# SDcard_eMMC.net
KiCad netlist of a schematic drawn in Altium Designer
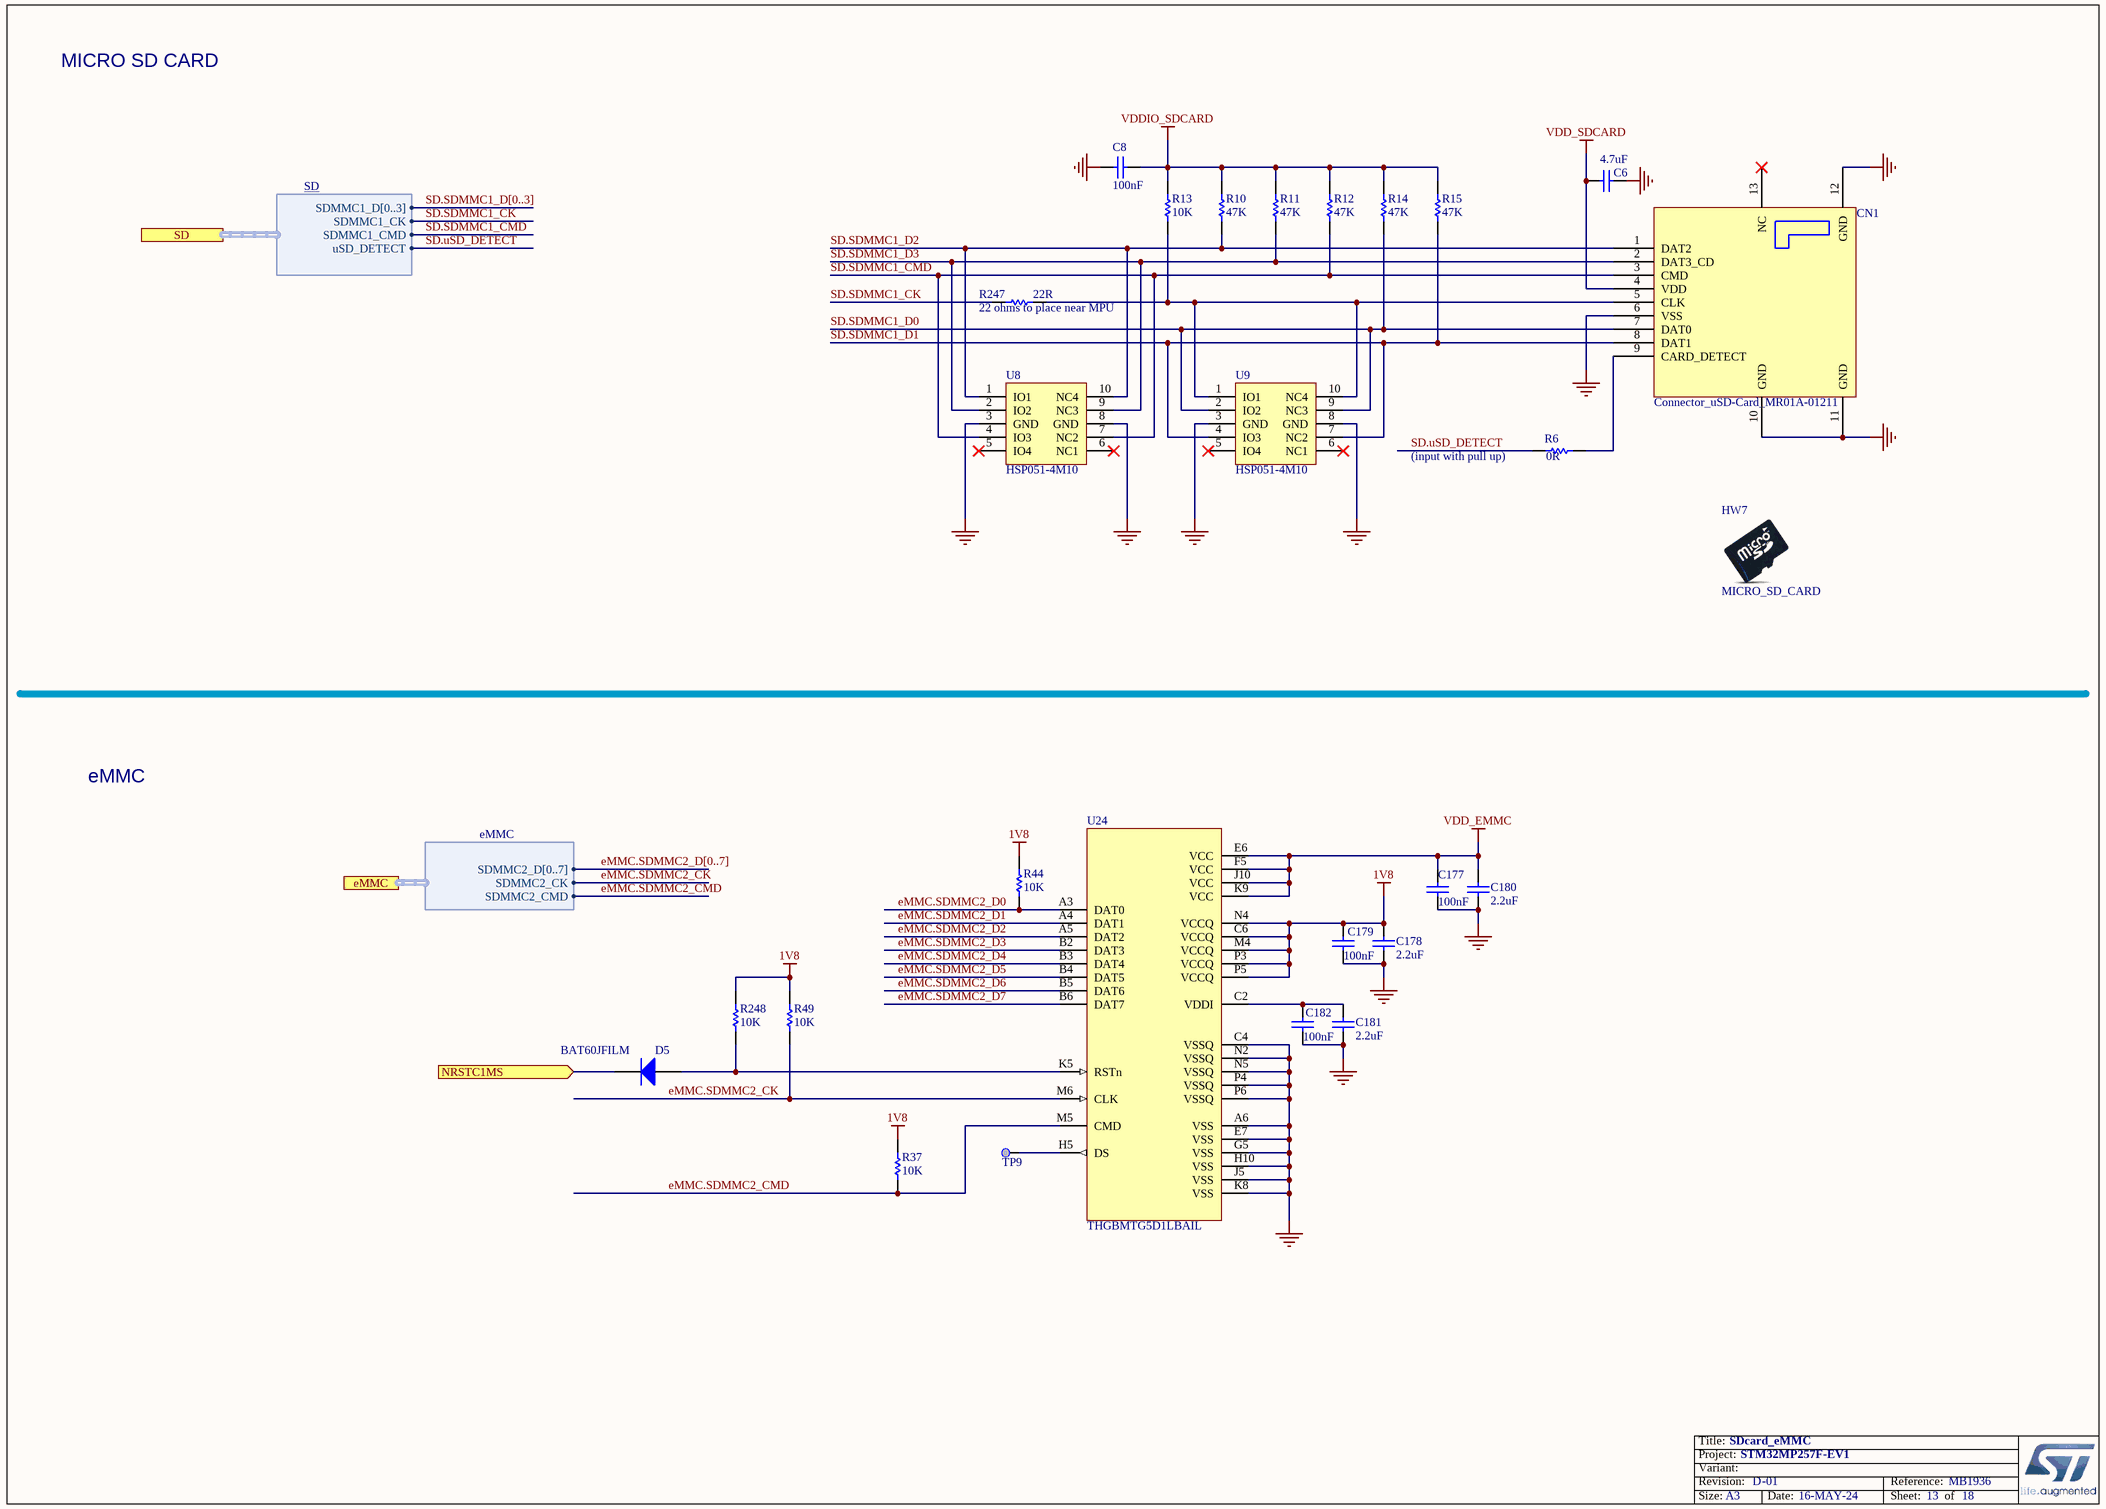
[diagram p0: SDcard_eMMC.SchDoc]

(export (version "E")
  (design (tool "Eeschema 10.0.6"))
  (components
    (comp (ref "C6")
      (value "4.7uF")
      (footprint "MCD_PARTS:C0402")
      (description "Capacitor, MLCC, 4.7uF, 6V3, X5R, 20%, 0402, T=0,5mm")
      (fields
        (field (name "INTERNAL_PART_NUMBER") "MCD-01356")
        (field (name "MANUFACTURER_PART_NUMBER") "GRM155R60J475ME47")
        (field (name "PROVIDED_BY") "SUBCO")
      )
      (libsource (lib "MCD_PARTS_database") (part "Capacitor"))
    )
    (comp (ref "C8")
      (value "100nF")
      (footprint "MCD_PARTS:C0402")
      (description "Capacitor, MLCC, 100nF, 16V, X7R, +/-10%, 0402, T=0.5mm")
      (fields (field (name "INTERNAL_PART_NUMBER") "MCD-00006") (field (name "MANUFACTURER") "YAGEO"))
      (libsource (lib "MCD_PARTS_database") (part "Capacitor"))
    )
    (comp (ref "C177")
      (value "100nF")
      (footprint "MCD_PARTS:C0402")
      (description "Capacitor, MLCC, 100nF, 16V, X7R, +/-10%, 0402, T=0.5mm")
      (fields (field (name "INTERNAL_PART_NUMBER") "MCD-00006") (field (name "MANUFACTURER") "YAGEO"))
      (libsource (lib "MCD_PARTS_database") (part "Capacitor"))
    )
    (comp (ref "C178")
      (value "2.2uF")
      (footprint "MCD_PARTS:C0402")
      (description "Capacitor, MLCC, 2.2uF, 6.3V, X5R, +/-10%, 0402, T=0.5mm")
      (fields (field (name "INTERNAL_PART_NUMBER") "MCD-02606") (field (name "MANUFACTURER") "YAGEO"))
      (libsource (lib "MCD_PARTS_database") (part "Capacitor"))
    )
    (comp (ref "C179")
      (value "100nF")
      (footprint "MCD_PARTS:C0402")
      (description "Capacitor, MLCC, 100nF, 16V, X7R, +/-10%, 0402, T=0.5mm")
      (fields (field (name "INTERNAL_PART_NUMBER") "MCD-00006") (field (name "MANUFACTURER") "YAGEO"))
      (libsource (lib "MCD_PARTS_database") (part "Capacitor"))
    )
    (comp (ref "C180")
      (value "2.2uF")
      (footprint "MCD_PARTS:C0402")
      (description "Capacitor, MLCC, 2.2uF, 6.3V, X5R, +/-10%, 0402, T=0.5mm")
      (fields (field (name "INTERNAL_PART_NUMBER") "MCD-02606") (field (name "MANUFACTURER") "YAGEO"))
      (libsource (lib "MCD_PARTS_database") (part "Capacitor"))
    )
    (comp (ref "C181")
      (value "2.2uF")
      (footprint "MCD_PARTS:C0402")
      (description "Capacitor, MLCC, 2.2uF, 6.3V, X5R, +/-10%, 0402, T=0.5mm")
      (fields (field (name "INTERNAL_PART_NUMBER") "MCD-02606") (field (name "MANUFACTURER") "YAGEO"))
      (libsource (lib "MCD_PARTS_database") (part "Capacitor"))
    )
    (comp (ref "C182")
      (value "100nF")
      (footprint "MCD_PARTS:C0402")
      (description "Capacitor, MLCC, 100nF, 16V, X7R, +/-10%, 0402, T=0.5mm")
      (fields (field (name "INTERNAL_PART_NUMBER") "MCD-00006") (field (name "MANUFACTURER") "YAGEO"))
      (libsource (lib "MCD_PARTS_database") (part "Capacitor"))
    )
    (comp (ref "CN1")
      (value "Connector_uSD-Card_MR01A-01211")
      (footprint "MCD_PARTS:CON_MICROSD_ATOM_MR01A-01211")
      (description "Connector_uSD Card, Top Mnt Push-Push")
      (fields (field (name "INTERNAL_PART_NUMBER") "MCD-00653") (field (name "MANUFACTURER") "ATOM"))
      (libsource (lib "MCD_PARTS_database") (part "MR01A-01211"))
    )
    (comp (ref "D5")
      (value "BAT60JFILM")
      (footprint "MCD_PARTS:DIO_SOD323")
      (fields
        (field (name "INTERNAL_PART_NUMBER") "MCD-00034")
        (field (name "BMS_PART_NUMBER") "9151097")
        (field (name "MANUFACTURER") "STMICROELECTRONICS")
      )
      (libsource (lib "MCD_PARTS_database") (part "BAT60JFILM"))
    )
    (comp (ref "HW7")
      (value "MICRO_SD_CARD")
      (description "MICRO_SD_CARD, SANDISK, 16GB, Class10, 3V")
      (fields (field (name "INTERNAL_PART_NUMBER") "MCD-03307") (field (name "MANUFACTURER") "SANDISK"))
      (libsource (lib "MCD_PARTS_database") (part "Micro_SD_card"))
    )
    (comp (ref "R6")
      (value "0R")
      (footprint "MCD_PARTS:R0402")
      (description "Resistor,0R,0402,5%,1/16W")
      (fields
        (field (name "INTERNAL_PART_NUMBER") "MCD-00052")
        (field (name "MANUFACTURER_PART_NUMBER") "RC0402JR-070RL")
        (field (name "PROVIDED_BY") "SUBCO")
      )
      (libsource (lib "MCD_PARTS_database") (part "Resistor"))
    )
    (comp (ref "R10")
      (value "47K")
      (footprint "MCD_PARTS:R0402")
      (description "Resistor,47K,0402,1%,1/16W")
      (fields
        (field (name "INTERNAL_PART_NUMBER") "MCD-00063")
        (field (name "MANUFACTURER_PART_NUMBER") "RC0402FR-0747KL")
        (field (name "PROVIDED_BY") "SUBCO")
      )
      (libsource (lib "MCD_PARTS_database") (part "Resistor"))
    )
    (comp (ref "R11")
      (value "47K")
      (footprint "MCD_PARTS:R0402")
      (description "Resistor,47K,0402,1%,1/16W")
      (fields
        (field (name "INTERNAL_PART_NUMBER") "MCD-00063")
        (field (name "MANUFACTURER_PART_NUMBER") "RC0402FR-0747KL")
        (field (name "PROVIDED_BY") "SUBCO")
      )
      (libsource (lib "MCD_PARTS_database") (part "Resistor"))
    )
    (comp (ref "R12")
      (value "47K")
      (footprint "MCD_PARTS:R0402")
      (description "Resistor,47K,0402,1%,1/16W")
      (fields
        (field (name "INTERNAL_PART_NUMBER") "MCD-00063")
        (field (name "MANUFACTURER_PART_NUMBER") "RC0402FR-0747KL")
        (field (name "PROVIDED_BY") "SUBCO")
      )
      (libsource (lib "MCD_PARTS_database") (part "Resistor"))
    )
    (comp (ref "R13")
      (value "10K")
      (footprint "MCD_PARTS:R0402")
      (description "Resistor,10K,0402,1%,1/16W")
      (fields
        (field (name "INTERNAL_PART_NUMBER") "MCD-00053")
        (field (name "MANUFACTURER_PART_NUMBER") "RC0402FR-0710KL")
        (field (name "PROVIDED_BY") "SUBCO")
      )
      (libsource (lib "MCD_PARTS_database") (part "Resistor"))
    )
    (comp (ref "R14")
      (value "47K")
      (footprint "MCD_PARTS:R0402")
      (description "Resistor,47K,0402,1%,1/16W")
      (fields
        (field (name "INTERNAL_PART_NUMBER") "MCD-00063")
        (field (name "MANUFACTURER_PART_NUMBER") "RC0402FR-0747KL")
        (field (name "PROVIDED_BY") "SUBCO")
      )
      (libsource (lib "MCD_PARTS_database") (part "Resistor"))
    )
    (comp (ref "R15")
      (value "47K")
      (footprint "MCD_PARTS:R0402")
      (description "Resistor,47K,0402,1%,1/16W")
      (fields
        (field (name "INTERNAL_PART_NUMBER") "MCD-00063")
        (field (name "MANUFACTURER_PART_NUMBER") "RC0402FR-0747KL")
        (field (name "PROVIDED_BY") "SUBCO")
      )
      (libsource (lib "MCD_PARTS_database") (part "Resistor"))
    )
    (comp (ref "R37")
      (value "10K")
      (footprint "MCD_PARTS:R0402")
      (description "Resistor,10K,0402,1%,1/16W")
      (fields
        (field (name "INTERNAL_PART_NUMBER") "MCD-00053")
        (field (name "MANUFACTURER_PART_NUMBER") "RC0402FR-0710KL")
        (field (name "PROVIDED_BY") "SUBCO")
      )
      (libsource (lib "MCD_PARTS_database") (part "Resistor"))
    )
    (comp (ref "R44")
      (value "10K")
      (footprint "MCD_PARTS:R0402")
      (description "Resistor,10K,0402,1%,1/16W")
      (fields
        (field (name "INTERNAL_PART_NUMBER") "MCD-00053")
        (field (name "MANUFACTURER_PART_NUMBER") "RC0402FR-0710KL")
        (field (name "PROVIDED_BY") "SUBCO")
      )
      (libsource (lib "MCD_PARTS_database") (part "Resistor"))
    )
    (comp (ref "R49")
      (value "10K")
      (footprint "MCD_PARTS:R0402")
      (description "Resistor,10K,0402,1%,1/16W")
      (fields
        (field (name "INTERNAL_PART_NUMBER") "MCD-00053")
        (field (name "MANUFACTURER_PART_NUMBER") "RC0402FR-0710KL")
        (field (name "PROVIDED_BY") "SUBCO")
      )
      (libsource (lib "MCD_PARTS_database") (part "Resistor"))
    )
    (comp (ref "R247")
      (value "22R")
      (footprint "MCD_PARTS:R0201_H0P23")
      (description "Resistor, 22R, 0201, +/-1%, 1/20W")
      (fields
        (field (name "INTERNAL_PART_NUMBER") "MCD-02978")
        (field (name "MANUFACTURER_PART_NUMBER") "RC0201FR-0722RL")
      )
      (libsource (lib "MCD_PARTS_database") (part "Resistor"))
    )
    (comp (ref "R248")
      (value "10K")
      (footprint "MCD_PARTS:R0402")
      (description "Resistor,10K,0402,1%,1/16W")
      (fields
        (field (name "INTERNAL_PART_NUMBER") "MCD-00053")
        (field (name "MANUFACTURER_PART_NUMBER") "RC0402FR-0710KL")
        (field (name "PROVIDED_BY") "SUBCO")
      )
      (libsource (lib "MCD_PARTS_database") (part "Resistor"))
    )
    (comp (ref "TP9")
      (value "Test Point")
      (footprint "MCD_PARTS:TP_SMD_1MM")
      (description "Test Point 1mm")
      (fields
        (field (name "INTERNAL_PART_NUMBER") "MCD-00074")
        (field (name "MANUFACTURER_PART_NUMBER") "n/a")
      )
      (libsource (lib "MCD_PARTS_database") (part "Test Point"))
    )
    (comp (ref "U8")
      (value "HSP051-4M10")
      (footprint "MCD_PARTS:ESD_UQFN-10L_2P5X1_P050")
      (description "4-line ESD protection for high speed lines")
      (fields
        (field (name "INTERNAL_PART_NUMBER") "MCD-00667")
        (field (name "MANUFACTURER") "STMICROELECTRONICS")
        (field (name "PROVIDED_BY") "SUBCO with ST control")
      )
      (libsource (lib "MCD_PARTS_database") (part "HSP051-4M10"))
    )
    (comp (ref "U9")
      (value "HSP051-4M10")
      (footprint "MCD_PARTS:ESD_UQFN-10L_2P5X1_P050")
      (description "4-line ESD protection for high speed lines")
      (fields
        (field (name "INTERNAL_PART_NUMBER") "MCD-00667")
        (field (name "MANUFACTURER") "STMICROELECTRONICS")
        (field (name "PROVIDED_BY") "SUBCO with ST control")
      )
      (libsource (lib "MCD_PARTS_database") (part "HSP051-4M10"))
    )
    (comp (ref "U24")
      (value "THGBMTG5D1LBAIL")
      (footprint "MCD_PARTS:ICC_P-WFBGA153_13X11P5_P050")
      (description "Memory, eMMC, 4GB, 15nm ,WFBGA , 153 pins")
      (fields (field (name "INTERNAL_PART_NUMBER") "MCD-02799") (field (name "MANUFACTURER") "KIOXIA"))
      (libsource (lib "MCD_PARTS_database") (part "eMMC_THGBMTG5D1LBAIL"))
    )
  )
  (nets
    (net (code "3") (name "/NRSTC1MS") (class "Default")
      (node (ref "D5") (pin "2") (pinfunction "K_2") (pintype "passive"))
    )
    (net (code "4") (name "/SD.SDMMC1_CK") (class "Default")
      (node (ref "R247") (pin "1") (pinfunction "1_1") (pintype "passive"))
    )
    (net (code "5") (name "/SD.SDMMC1_CMD") (class "Default")
      (node (ref "CN1") (pin "3") (pinfunction "CMD_3") (pintype "passive"))
      (node (ref "R12") (pin "1") (pinfunction "1_1") (pintype "passive"))
      (node (ref "U8") (pin "4") (pinfunction "IO3_4") (pintype "passive"))
      (node (ref "U8") (pin "7") (pinfunction "NC2_7") (pintype "passive"))
    )
    (net (code "6") (name "/SD.SDMMC1_D0") (class "Default")
      (node (ref "CN1") (pin "7") (pinfunction "DAT0_7") (pintype "passive"))
      (node (ref "R14") (pin "1") (pinfunction "1_1") (pintype "passive"))
      (node (ref "U9") (pin "2") (pinfunction "IO2_2") (pintype "passive"))
      (node (ref "U9") (pin "9") (pinfunction "NC3_9") (pintype "passive"))
    )
    (net (code "7") (name "/SD.SDMMC1_D1") (class "Default")
      (node (ref "CN1") (pin "8") (pinfunction "DAT1_8") (pintype "passive"))
      (node (ref "R15") (pin "1") (pinfunction "1_1") (pintype "passive"))
      (node (ref "U9") (pin "4") (pinfunction "IO3_4") (pintype "passive"))
      (node (ref "U9") (pin "7") (pinfunction "NC2_7") (pintype "passive"))
    )
    (net (code "8") (name "/SD.SDMMC1_D2") (class "Default")
      (node (ref "CN1") (pin "1") (pinfunction "DAT2_1") (pintype "passive"))
      (node (ref "R10") (pin "1") (pinfunction "1_1") (pintype "passive"))
      (node (ref "U8") (pin "1") (pinfunction "IO1_1") (pintype "passive"))
      (node (ref "U8") (pin "10") (pinfunction "NC4_10") (pintype "passive"))
    )
    (net (code "9") (name "/SD.SDMMC1_D3") (class "Default")
      (node (ref "CN1") (pin "2") (pinfunction "DAT3_CD_2") (pintype "passive"))
      (node (ref "R11") (pin "1") (pinfunction "1_1") (pintype "passive"))
      (node (ref "U8") (pin "2") (pinfunction "IO2_2") (pintype "passive"))
      (node (ref "U8") (pin "9") (pinfunction "NC3_9") (pintype "passive"))
    )
    (net (code "10") (name "/SD.uSD_DETECT") (class "Default")
      (node (ref "R6") (pin "1") (pinfunction "1_1") (pintype "passive"))
    )
    (net (code "12") (name "/eMMC.SDMMC2_CK") (class "Default")
      (node (ref "R49") (pin "1") (pinfunction "1_1") (pintype "passive"))
      (node (ref "U24") (pin "M6") (pinfunction "CLK_M6") (pintype "input"))
    )
    (net (code "13") (name "/eMMC.SDMMC2_CMD") (class "Default")
      (node (ref "R37") (pin "1") (pinfunction "1_1") (pintype "passive"))
      (node (ref "U24") (pin "M5") (pinfunction "CMD_M5") (pintype "passive"))
    )
    (net (code "14") (name "/eMMC.SDMMC2_D0") (class "Default")
      (node (ref "R44") (pin "1") (pinfunction "1_1") (pintype "passive"))
      (node (ref "U24") (pin "A3") (pinfunction "DAT0_A3") (pintype "passive"))
    )
    (net (code "15") (name "/eMMC.SDMMC2_D1") (class "Default")
      (node (ref "U24") (pin "A4") (pinfunction "DAT1_A4") (pintype "passive"))
    )
    (net (code "16") (name "/eMMC.SDMMC2_D2") (class "Default")
      (node (ref "U24") (pin "A5") (pinfunction "DAT2_A5") (pintype "passive"))
    )
    (net (code "17") (name "/eMMC.SDMMC2_D3") (class "Default")
      (node (ref "U24") (pin "B2") (pinfunction "DAT3_B2") (pintype "passive"))
    )
    (net (code "18") (name "/eMMC.SDMMC2_D4") (class "Default")
      (node (ref "U24") (pin "B3") (pinfunction "DAT4_B3") (pintype "passive"))
    )
    (net (code "19") (name "/eMMC.SDMMC2_D5") (class "Default")
      (node (ref "U24") (pin "B4") (pinfunction "DAT5_B4") (pintype "passive"))
    )
    (net (code "20") (name "/eMMC.SDMMC2_D6") (class "Default")
      (node (ref "U24") (pin "B5") (pinfunction "DAT6_B5") (pintype "passive"))
    )
    (net (code "21") (name "/eMMC.SDMMC2_D7") (class "Default")
      (node (ref "U24") (pin "B6") (pinfunction "DAT7_B6") (pintype "passive"))
    )
    (net (code "25") (name "1V8") (class "Default")
      (node (ref "C178") (pin "2") (pinfunction "2_2") (pintype "passive"))
      (node (ref "C179") (pin "2") (pinfunction "2_2") (pintype "passive"))
      (node (ref "R248") (pin "2") (pinfunction "2_2") (pintype "passive"))
      (node (ref "R37") (pin "2") (pinfunction "2_2") (pintype "passive"))
      (node (ref "R44") (pin "2") (pinfunction "2_2") (pintype "passive"))
      (node (ref "R49") (pin "2") (pinfunction "2_2") (pintype "passive"))
      (node (ref "U24") (pin "C6") (pinfunction "VCCQ_C6") (pintype "passive"))
      (node (ref "U24") (pin "M4") (pinfunction "VCCQ_M4") (pintype "passive"))
      (node (ref "U24") (pin "N4") (pinfunction "VCCQ_N4") (pintype "passive"))
      (node (ref "U24") (pin "P3") (pinfunction "VCCQ_P3") (pintype "passive"))
      (node (ref "U24") (pin "P5") (pinfunction "VCCQ_P5") (pintype "passive"))
    )
    (net (code "26") (name "GND") (class "Default")
      (node (ref "C177") (pin "1") (pinfunction "1_1") (pintype "passive"))
      (node (ref "C178") (pin "1") (pinfunction "1_1") (pintype "passive"))
      (node (ref "C179") (pin "1") (pinfunction "1_1") (pintype "passive"))
      (node (ref "C180") (pin "1") (pinfunction "1_1") (pintype "passive"))
      (node (ref "C181") (pin "1") (pinfunction "1_1") (pintype "passive"))
      (node (ref "C182") (pin "1") (pinfunction "1_1") (pintype "passive"))
      (node (ref "C6") (pin "1") (pinfunction "1_1") (pintype "passive"))
      (node (ref "C8") (pin "1") (pinfunction "1_1") (pintype "passive"))
      (node (ref "CN1") (pin "10") (pinfunction "GND_10") (pintype "passive"))
      (node (ref "CN1") (pin "11") (pinfunction "GND_11") (pintype "passive"))
      (node (ref "CN1") (pin "12") (pinfunction "GND_12") (pintype "passive"))
      (node (ref "CN1") (pin "6") (pinfunction "VSS_6") (pintype "passive"))
      (node (ref "U24") (pin "A6") (pinfunction "VSS_A6") (pintype "passive"))
      (node (ref "U24") (pin "C4") (pinfunction "VSSQ_C4") (pintype "passive"))
      (node (ref "U24") (pin "E7") (pinfunction "VSS_E7") (pintype "passive"))
      (node (ref "U24") (pin "G5") (pinfunction "VSS_G5") (pintype "passive"))
      (node (ref "U24") (pin "H10") (pinfunction "VSS_H10") (pintype "passive"))
      (node (ref "U24") (pin "J5") (pinfunction "VSS_J5") (pintype "passive"))
      (node (ref "U24") (pin "K8") (pinfunction "VSS_K8") (pintype "passive"))
      (node (ref "U24") (pin "N2") (pinfunction "VSSQ_N2") (pintype "passive"))
      (node (ref "U24") (pin "N5") (pinfunction "VSSQ_N5") (pintype "passive"))
      (node (ref "U24") (pin "P4") (pinfunction "VSSQ_P4") (pintype "passive"))
      (node (ref "U24") (pin "P6") (pinfunction "VSSQ_P6") (pintype "passive"))
      (node (ref "U8") (pin "3") (pinfunction "GND_3") (pintype "passive"))
      (node (ref "U8") (pin "8") (pinfunction "GND_8") (pintype "passive"))
      (node (ref "U9") (pin "3") (pinfunction "GND_3") (pintype "passive"))
      (node (ref "U9") (pin "8") (pinfunction "GND_8") (pintype "passive"))
    )
    (net (code "27") (name "Net-(CN1-CARD_DETECT)") (class "Default")
      (node (ref "CN1") (pin "9") (pinfunction "CARD_DETECT_9") (pintype "passive"))
      (node (ref "R6") (pin "2") (pinfunction "2_2") (pintype "passive"))
    )
    (net (code "28") (name "Net-(CN1-CLK)") (class "Default")
      (node (ref "CN1") (pin "5") (pinfunction "CLK_5") (pintype "passive"))
      (node (ref "R13") (pin "1") (pinfunction "1_1") (pintype "passive"))
      (node (ref "R247") (pin "2") (pinfunction "2_2") (pintype "passive"))
      (node (ref "U9") (pin "1") (pinfunction "IO1_1") (pintype "passive"))
      (node (ref "U9") (pin "10") (pinfunction "NC4_10") (pintype "passive"))
    )
    (net (code "29") (name "Net-(D5-A)") (class "Default")
      (node (ref "D5") (pin "1") (pinfunction "A_1") (pintype "passive"))
      (node (ref "R248") (pin "1") (pinfunction "1_1") (pintype "passive"))
      (node (ref "U24") (pin "K5") (pinfunction "RSTn_K5") (pintype "input"))
    )
    (net (code "30") (name "Net-(U24-DS)") (class "Default")
      (node (ref "TP9") (pin "1") (pinfunction "1_1") (pintype "passive"))
      (node (ref "U24") (pin "H5") (pinfunction "DS_H5") (pintype "output"))
    )
    (net (code "31") (name "Net-(U24-VDDI)") (class "Default")
      (node (ref "C181") (pin "2") (pinfunction "2_2") (pintype "passive"))
      (node (ref "C182") (pin "2") (pinfunction "2_2") (pintype "passive"))
      (node (ref "U24") (pin "C2") (pinfunction "VDDI_C2") (pintype "passive"))
    )
    (net (code "32") (name "VDDIO_SDCARD") (class "Default")
      (node (ref "C8") (pin "2") (pinfunction "2_2") (pintype "passive"))
      (node (ref "R10") (pin "2") (pinfunction "2_2") (pintype "passive"))
      (node (ref "R11") (pin "2") (pinfunction "2_2") (pintype "passive"))
      (node (ref "R12") (pin "2") (pinfunction "2_2") (pintype "passive"))
      (node (ref "R13") (pin "2") (pinfunction "2_2") (pintype "passive"))
      (node (ref "R14") (pin "2") (pinfunction "2_2") (pintype "passive"))
      (node (ref "R15") (pin "2") (pinfunction "2_2") (pintype "passive"))
    )
    (net (code "33") (name "VDD_EMMC") (class "Default")
      (node (ref "C177") (pin "2") (pinfunction "2_2") (pintype "passive"))
      (node (ref "C180") (pin "2") (pinfunction "2_2") (pintype "passive"))
      (node (ref "U24") (pin "E6") (pinfunction "VCC_E6") (pintype "passive"))
      (node (ref "U24") (pin "F5") (pinfunction "VCC_F5") (pintype "passive"))
      (node (ref "U24") (pin "J10") (pinfunction "VCC_J10") (pintype "passive"))
      (node (ref "U24") (pin "K9") (pinfunction "VCC_K9") (pintype "passive"))
    )
    (net (code "34") (name "VDD_SDCARD") (class "Default")
      (node (ref "C6") (pin "2") (pinfunction "2_2") (pintype "passive"))
      (node (ref "CN1") (pin "4") (pinfunction "VDD_4") (pintype "passive"))
    )
    (net (code "35") (name "unconnected-(CN1-NC-Pad13)") (class "Default")
      (node (ref "CN1") (pin "13") (pinfunction "NC_13") (pintype "passive+no_connect"))
    )
    (net (code "36") (name "unconnected-(U8-IO4-Pad5)") (class "Default")
      (node (ref "U8") (pin "5") (pinfunction "IO4_5") (pintype "passive+no_connect"))
    )
    (net (code "37") (name "unconnected-(U8-NC1-Pad6)") (class "Default")
      (node (ref "U8") (pin "6") (pinfunction "NC1_6") (pintype "passive+no_connect"))
    )
    (net (code "38") (name "unconnected-(U9-IO4-Pad5)") (class "Default")
      (node (ref "U9") (pin "5") (pinfunction "IO4_5") (pintype "passive+no_connect"))
    )
    (net (code "39") (name "unconnected-(U9-NC1-Pad6)") (class "Default")
      (node (ref "U9") (pin "6") (pinfunction "NC1_6") (pintype "passive+no_connect"))
    )
  )
)
